# hacker-boards-refactor.net
KiCad netlist of a schematic drawn in EAGLE
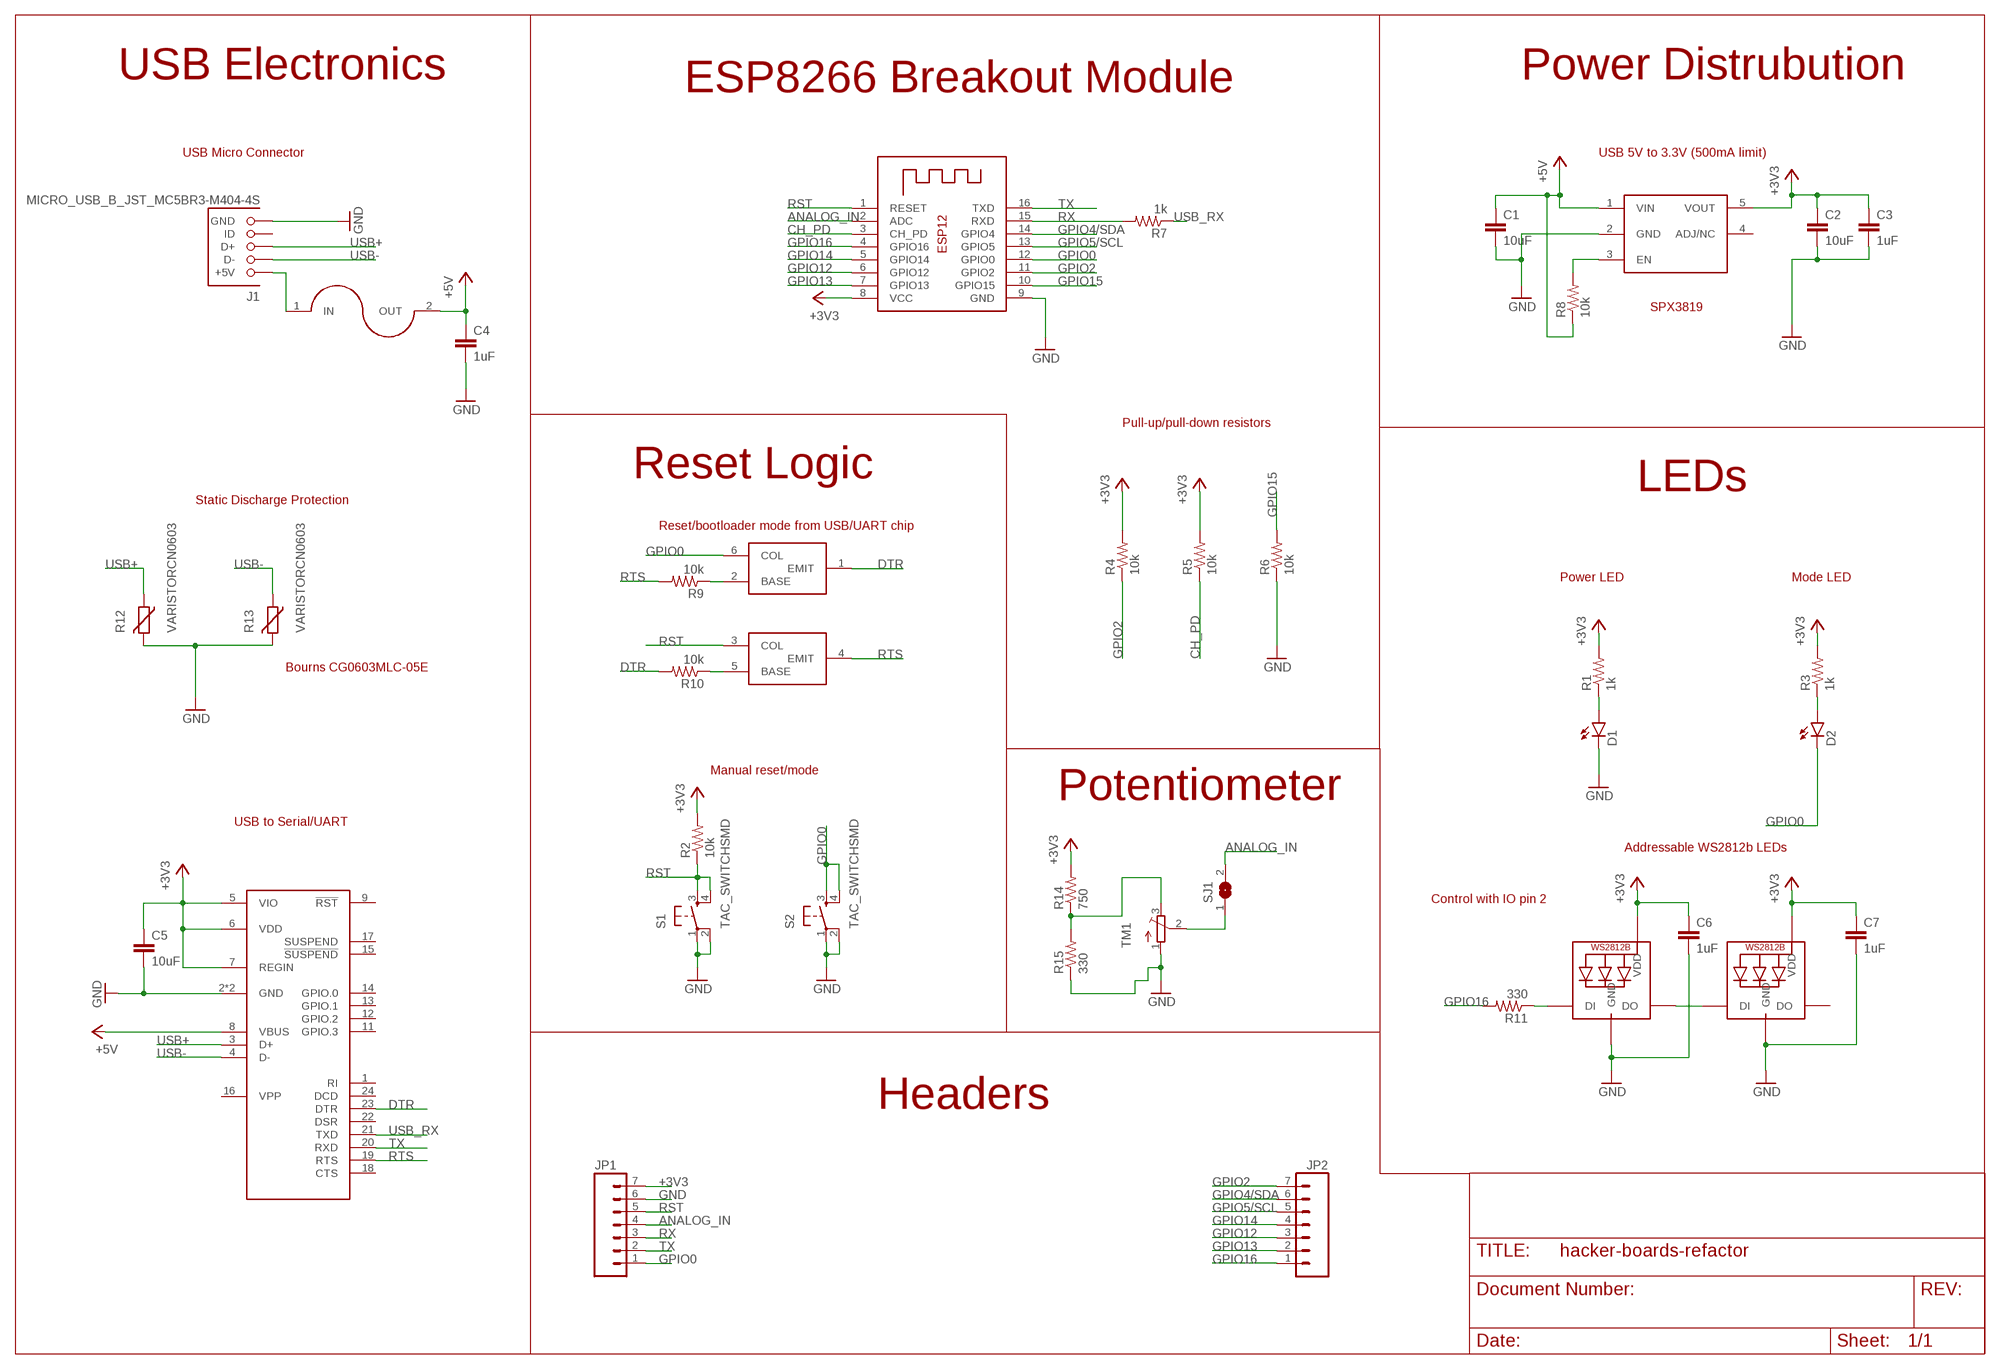
[diagram p0: schematic, sheet 1]

(export (version "E")
  (design (tool "Eeschema 10.0.6"))
  (components
    (comp (ref "C1")
      (value "10uF")
      (footprint "eagle-import:C0805")
      (libsource (lib "eagle-import") (part "C0805"))
    )
    (comp (ref "C2")
      (value "10uF")
      (footprint "eagle-import:C0805")
      (libsource (lib "eagle-import") (part "C0805"))
    )
    (comp (ref "C3")
      (value "1uF")
      (footprint "eagle-import:C0805")
      (libsource (lib "eagle-import") (part "C0805"))
    )
    (comp (ref "C4")
      (value "1uF")
      (footprint "eagle-import:C0805")
      (libsource (lib "eagle-import") (part "C0805"))
    )
    (comp (ref "C5")
      (value "10uF")
      (footprint "eagle-import:C0805")
      (libsource (lib "eagle-import") (part "C0805"))
    )
    (comp (ref "C6")
      (value "1uF")
      (footprint "eagle-import:C0805")
      (libsource (lib "eagle-import") (part "C0805"))
    )
    (comp (ref "C7")
      (value "1uF")
      (footprint "eagle-import:C0805")
      (libsource (lib "eagle-import") (part "C0805"))
    )
    (comp (ref "D1")
      (value "LED0603")
      (footprint "eagle-import:LED-0603")
      (libsource (lib "eagle-import") (part "LED0603"))
    )
    (comp (ref "D2")
      (value "LED0603")
      (footprint "eagle-import:LED-0603")
      (libsource (lib "eagle-import") (part "LED0603"))
    )
    (comp (ref "J1")
      (value "MICRO_USB_B_JST_MC5BR3-M404-4S")
      (footprint "eagle-import:USB_MICRO_B-JST-MC5BR3-M404-4S-TB")
      (libsource (lib "eagle-import") (part "MICRO_USB_B_JST_MC5BR3-M404-4S"))
    )
    (comp (ref "JP1")
      (value "M07LONGPADS")
      (footprint "eagle-import:1X07_LONGPADS")
      (libsource (lib "eagle-import") (part "M07LONGPADS"))
    )
    (comp (ref "JP2")
      (value "M07LONGPADS")
      (footprint "eagle-import:1X07_LONGPADS")
      (libsource (lib "eagle-import") (part "M07LONGPADS"))
    )
    (comp (ref "LED1")
      (value "WS2812B5050")
      (footprint "eagle-import:WS2812B")
      (libsource (lib "eagle-import") (part "WS2812B5050"))
    )
    (comp (ref "LED2")
      (value "WS2812B5050")
      (footprint "eagle-import:WS2812B")
      (libsource (lib "eagle-import") (part "WS2812B5050"))
    )
    (comp (ref "R1")
      (value "1k")
      (footprint "eagle-import:R0805")
      (libsource (lib "eagle-import") (part "R-US_R0805"))
    )
    (comp (ref "R2")
      (value "10k")
      (footprint "eagle-import:R0805")
      (libsource (lib "eagle-import") (part "R-US_R0805"))
    )
    (comp (ref "R3")
      (value "1k")
      (footprint "eagle-import:R0805")
      (libsource (lib "eagle-import") (part "R-US_R0805"))
    )
    (comp (ref "R4")
      (value "10k")
      (footprint "eagle-import:R0805")
      (libsource (lib "eagle-import") (part "R-US_R0805"))
    )
    (comp (ref "R5")
      (value "10k")
      (footprint "eagle-import:R0805")
      (libsource (lib "eagle-import") (part "R-US_R0805"))
    )
    (comp (ref "R6")
      (value "10k")
      (footprint "eagle-import:R0805")
      (libsource (lib "eagle-import") (part "R-US_R0805"))
    )
    (comp (ref "R7")
      (value "1k")
      (footprint "eagle-import:R0805")
      (libsource (lib "eagle-import") (part "R-US_R0805"))
    )
    (comp (ref "R8")
      (value "10k")
      (footprint "eagle-import:R0805")
      (libsource (lib "eagle-import") (part "R-US_R0805"))
    )
    (comp (ref "R9")
      (value "10k")
      (footprint "eagle-import:R0805")
      (libsource (lib "eagle-import") (part "R-US_R0805"))
    )
    (comp (ref "R10")
      (value "10k")
      (footprint "eagle-import:R0805")
      (libsource (lib "eagle-import") (part "R-US_R0805"))
    )
    (comp (ref "R11")
      (value "330")
      (footprint "eagle-import:R0805")
      (libsource (lib "eagle-import") (part "R-US_R0805"))
    )
    (comp (ref "R12")
      (value "VARISTORCN0603")
      (footprint "eagle-import:CT_CN0603")
      (libsource (lib "eagle-import") (part "VARISTORCN0603"))
    )
    (comp (ref "R13")
      (value "VARISTORCN0603")
      (footprint "eagle-import:CT_CN0603")
      (libsource (lib "eagle-import") (part "VARISTORCN0603"))
    )
    (comp (ref "R14")
      (value "750")
      (footprint "eagle-import:R0805")
      (libsource (lib "eagle-import") (part "R-US_R0805"))
    )
    (comp (ref "R15")
      (value "330")
      (footprint "eagle-import:R0805")
      (libsource (lib "eagle-import") (part "R-US_R0805"))
    )
    (comp (ref "S1")
      (value "TAC_SWITCHSMD")
      (footprint "eagle-import:TACTILE-SWITCH-SMD")
      (libsource (lib "eagle-import") (part "TAC_SWITCHSMD"))
    )
    (comp (ref "S2")
      (value "TAC_SWITCHSMD")
      (footprint "eagle-import:TACTILE-SWITCH-SMD")
      (libsource (lib "eagle-import") (part "TAC_SWITCHSMD"))
    )
    (comp (ref "SJ1") (value "SJ") (footprint "eagle-import:SJ") (libsource (lib "eagle-import") (part "SJ")))
    (comp (ref "TM1")
      (value "TRIMPOTTC33X")
      (footprint "eagle-import:TC33X")
      (libsource (lib "eagle-import") (part "TRIMPOTTC33X"))
    )
    (comp (ref "U$1")
      (value "USB-FUSE")
      (footprint "eagle-import:L1812")
      (libsource (lib "eagle-import") (part "USB-FUSE"))
    )
    (comp (ref "U$2")
      (value "AP2112")
      (footprint "eagle-import:SOT23-5L")
      (libsource (lib "eagle-import") (part "AP2112"))
    )
    (comp (ref "U$3")
      (value "CP2104")
      (footprint "eagle-import:QFN24_4X4")
      (libsource (lib "eagle-import") (part "CP2104"))
    )
    (comp (ref "U$4")
      (value "MBT3904DW1T1G")
      (footprint "eagle-import:SOT363")
      (libsource (lib "eagle-import") (part "MBT3904DW1T1G"))
    )
    (comp (ref "X1")
      (value "ESP-12")
      (footprint "eagle-import:ESP-12")
      (libsource (lib "eagle-import") (part "ESP-12"))
    )
  )
  (nets
    (net (code "1") (name "+3V3") (class "Default")
      (node (ref "C2") (pin "1") (pinfunction "1_1") (pintype "passive"))
      (node (ref "C3") (pin "1") (pinfunction "1_1") (pintype "passive"))
      (node (ref "C5") (pin "1") (pinfunction "1_1") (pintype "passive"))
      (node (ref "C6") (pin "1") (pinfunction "1_1") (pintype "passive"))
      (node (ref "C7") (pin "1") (pinfunction "1_1") (pintype "passive"))
      (node (ref "JP1") (pin "7") (pinfunction "7_7") (pintype "passive"))
      (node (ref "LED1") (pin "1-VDD") (pinfunction "VDD_1-VDD") (pintype "power_in"))
      (node (ref "LED2") (pin "1-VDD") (pinfunction "VDD_1-VDD") (pintype "power_in"))
      (node (ref "R1") (pin "2") (pinfunction "2_2") (pintype "passive"))
      (node (ref "R14") (pin "2") (pinfunction "2_2") (pintype "passive"))
      (node (ref "R2") (pin "2") (pinfunction "2_2") (pintype "passive"))
      (node (ref "R3") (pin "2") (pinfunction "2_2") (pintype "passive"))
      (node (ref "R4") (pin "2") (pinfunction "2_2") (pintype "passive"))
      (node (ref "R5") (pin "2") (pinfunction "2_2") (pintype "passive"))
      (node (ref "U$2") (pin "5") (pinfunction "VOUT_5") (pintype "bidirectional"))
      (node (ref "U$3") (pin "5") (pinfunction "VIO_5") (pintype "bidirectional"))
      (node (ref "U$3") (pin "6") (pinfunction "VDD_6") (pintype "bidirectional"))
      (node (ref "U$3") (pin "7") (pinfunction "REGIN_7") (pintype "bidirectional"))
      (node (ref "X1") (pin "8") (pinfunction "VCC_8") (pintype "power_in"))
    )
    (net (code "2") (name "+5V") (class "Default")
      (node (ref "C1") (pin "1") (pinfunction "1_1") (pintype "passive"))
      (node (ref "C4") (pin "1") (pinfunction "1_1") (pintype "passive"))
      (node (ref "R8") (pin "1") (pinfunction "1_1") (pintype "passive"))
      (node (ref "U$1") (pin "2") (pinfunction "OUT_2") (pintype "bidirectional"))
      (node (ref "U$2") (pin "1") (pinfunction "VIN_1") (pintype "bidirectional"))
      (node (ref "U$3") (pin "8") (pinfunction "VBUS_8") (pintype "bidirectional"))
    )
    (net (code "3") (name "/ANALOG_IN") (class "Default")
      (node (ref "JP1") (pin "4") (pinfunction "4_4") (pintype "passive"))
      (node (ref "SJ1") (pin "2") (pinfunction "2_2") (pintype "passive"))
      (node (ref "X1") (pin "2") (pinfunction "ADC_2") (pintype "passive"))
    )
    (net (code "4") (name "/CH_PD") (class "Default")
      (node (ref "R5") (pin "1") (pinfunction "1_1") (pintype "passive"))
      (node (ref "X1") (pin "3") (pinfunction "CH_PD_3") (pintype "input"))
    )
    (net (code "5") (name "/DTR") (class "Default")
      (node (ref "R10") (pin "2") (pinfunction "2_2") (pintype "passive"))
      (node (ref "U$3") (pin "23") (pinfunction "DTR_23") (pintype "bidirectional"))
      (node (ref "U$4") (pin "1") (pinfunction "EMIT_1") (pintype "bidirectional"))
    )
    (net (code "6") (name "/GPIO0") (class "Default")
      (node (ref "D2") (pin "C") (pinfunction "C_C") (pintype "passive"))
      (node (ref "JP1") (pin "1") (pinfunction "1_1") (pintype "passive"))
      (node (ref "S2") (pin "3") (pinfunction "3_3") (pintype "passive"))
      (node (ref "S2") (pin "4") (pinfunction "4_4") (pintype "passive"))
      (node (ref "U$4") (pin "6") (pinfunction "COL_6") (pintype "bidirectional"))
      (node (ref "X1") (pin "12") (pinfunction "GPIO0_12") (pintype "bidirectional"))
    )
    (net (code "7") (name "/GPIO2") (class "Default")
      (node (ref "JP2") (pin "7") (pinfunction "7_7") (pintype "passive"))
      (node (ref "R4") (pin "1") (pinfunction "1_1") (pintype "passive"))
      (node (ref "X1") (pin "11") (pinfunction "GPIO2_11") (pintype "bidirectional"))
    )
    (net (code "8") (name "/GPIO4{slash}SDA") (class "Default")
      (node (ref "JP2") (pin "6") (pinfunction "6_6") (pintype "passive"))
      (node (ref "X1") (pin "14") (pinfunction "GPIO4_14") (pintype "bidirectional"))
    )
    (net (code "9") (name "/GPIO5{slash}SCL") (class "Default")
      (node (ref "JP2") (pin "5") (pinfunction "5_5") (pintype "passive"))
      (node (ref "X1") (pin "13") (pinfunction "GPIO5_13") (pintype "bidirectional"))
    )
    (net (code "10") (name "/GPIO12") (class "Default")
      (node (ref "JP2") (pin "3") (pinfunction "3_3") (pintype "passive"))
      (node (ref "X1") (pin "6") (pinfunction "GPIO12_6") (pintype "bidirectional"))
    )
    (net (code "11") (name "/GPIO13") (class "Default")
      (node (ref "JP2") (pin "2") (pinfunction "2_2") (pintype "passive"))
      (node (ref "X1") (pin "7") (pinfunction "GPIO13_7") (pintype "bidirectional"))
    )
    (net (code "12") (name "/GPIO14") (class "Default")
      (node (ref "JP2") (pin "4") (pinfunction "4_4") (pintype "passive"))
      (node (ref "X1") (pin "5") (pinfunction "GPIO14_5") (pintype "bidirectional"))
    )
    (net (code "13") (name "/GPIO15") (class "Default")
      (node (ref "R6") (pin "2") (pinfunction "2_2") (pintype "passive"))
      (node (ref "X1") (pin "10") (pinfunction "GPIO15_10") (pintype "bidirectional"))
    )
    (net (code "14") (name "/GPIO16") (class "Default")
      (node (ref "JP2") (pin "1") (pinfunction "1_1") (pintype "passive"))
      (node (ref "R11") (pin "2") (pinfunction "2_2") (pintype "passive"))
      (node (ref "X1") (pin "4") (pinfunction "GPIO16_4") (pintype "bidirectional"))
    )
    (net (code "15") (name "/RST") (class "Default")
      (node (ref "JP1") (pin "5") (pinfunction "5_5") (pintype "passive"))
      (node (ref "R2") (pin "1") (pinfunction "1_1") (pintype "passive"))
      (node (ref "S1") (pin "3") (pinfunction "3_3") (pintype "passive"))
      (node (ref "S1") (pin "4") (pinfunction "4_4") (pintype "passive"))
      (node (ref "U$4") (pin "3") (pinfunction "COL_3") (pintype "bidirectional"))
      (node (ref "X1") (pin "1") (pinfunction "RESET_1") (pintype "input"))
    )
    (net (code "16") (name "/RTS") (class "Default")
      (node (ref "R9") (pin "2") (pinfunction "2_2") (pintype "passive"))
      (node (ref "U$3") (pin "19") (pinfunction "RTS_19") (pintype "bidirectional"))
      (node (ref "U$4") (pin "4") (pinfunction "EMIT_4") (pintype "bidirectional"))
    )
    (net (code "17") (name "/RX") (class "Default")
      (node (ref "JP1") (pin "3") (pinfunction "3_3") (pintype "passive"))
      (node (ref "R7") (pin "2") (pinfunction "2_2") (pintype "passive"))
      (node (ref "X1") (pin "15") (pinfunction "RXD_15") (pintype "input"))
    )
    (net (code "18") (name "/TX") (class "Default")
      (node (ref "JP1") (pin "2") (pinfunction "2_2") (pintype "passive"))
      (node (ref "U$3") (pin "20") (pinfunction "RXD_20") (pintype "bidirectional"))
      (node (ref "X1") (pin "16") (pinfunction "TXD_16") (pintype "output"))
    )
    (net (code "19") (name "/USB+") (class "Default")
      (node (ref "J1") (pin "3") (pinfunction "D+_3") (pintype "bidirectional"))
      (node (ref "R12") (pin "1") (pinfunction "1_1") (pintype "passive"))
      (node (ref "U$3") (pin "3") (pinfunction "D+_3") (pintype "bidirectional"))
    )
    (net (code "20") (name "/USB-") (class "Default")
      (node (ref "J1") (pin "2") (pinfunction "D-_2") (pintype "bidirectional"))
      (node (ref "R13") (pin "1") (pinfunction "1_1") (pintype "passive"))
      (node (ref "U$3") (pin "4") (pinfunction "D-_4") (pintype "bidirectional"))
    )
    (net (code "21") (name "/USB_RX") (class "Default")
      (node (ref "R7") (pin "1") (pinfunction "1_1") (pintype "passive"))
      (node (ref "U$3") (pin "21") (pinfunction "TXD_21") (pintype "bidirectional"))
    )
    (net (code "22") (name "GND") (class "Default")
      (node (ref "C1") (pin "2") (pinfunction "2_2") (pintype "passive"))
      (node (ref "C2") (pin "2") (pinfunction "2_2") (pintype "passive"))
      (node (ref "C3") (pin "2") (pinfunction "2_2") (pintype "passive"))
      (node (ref "C4") (pin "2") (pinfunction "2_2") (pintype "passive"))
      (node (ref "C5") (pin "2") (pinfunction "2_2") (pintype "passive"))
      (node (ref "C6") (pin "2") (pinfunction "2_2") (pintype "passive"))
      (node (ref "C7") (pin "2") (pinfunction "2_2") (pintype "passive"))
      (node (ref "D1") (pin "C") (pinfunction "C_C") (pintype "passive"))
      (node (ref "J1") (pin "5") (pinfunction "GND_5") (pintype "bidirectional"))
      (node (ref "JP1") (pin "6") (pinfunction "6_6") (pintype "passive"))
      (node (ref "LED1") (pin "3-GND") (pinfunction "GND_3-GND") (pintype "power_in"))
      (node (ref "LED2") (pin "3-GND") (pinfunction "GND_3-GND") (pintype "power_in"))
      (node (ref "R12") (pin "2") (pinfunction "2_2") (pintype "passive"))
      (node (ref "R13") (pin "2") (pinfunction "2_2") (pintype "passive"))
      (node (ref "R15") (pin "1") (pinfunction "1_1") (pintype "passive"))
      (node (ref "R6") (pin "1") (pinfunction "1_1") (pintype "passive"))
      (node (ref "S1") (pin "1") (pinfunction "1_1") (pintype "passive"))
      (node (ref "S1") (pin "2") (pinfunction "2_2") (pintype "passive"))
      (node (ref "S2") (pin "1") (pinfunction "1_1") (pintype "passive"))
      (node (ref "S2") (pin "2") (pinfunction "2_2") (pintype "passive"))
      (node (ref "TM1") (pin "1") (pinfunction "A_1") (pintype "passive"))
      (node (ref "U$2") (pin "2") (pinfunction "GND_2") (pintype "bidirectional"))
      (node (ref "U$3") (pin "2") (pinfunction "GND_2") (pintype "bidirectional"))
      (node (ref "U$3") (pin "25") (pinfunction "GND_25") (pintype "bidirectional"))
      (node (ref "X1") (pin "9") (pinfunction "GND_9") (pintype "power_in"))
    )
    (net (code "23") (name "Net-(D1-PadA)") (class "Default")
      (node (ref "D1") (pin "A") (pinfunction "A_A") (pintype "passive"))
      (node (ref "R1") (pin "1") (pinfunction "1_1") (pintype "passive"))
    )
    (net (code "24") (name "Net-(D2-PadA)") (class "Default")
      (node (ref "D2") (pin "A") (pinfunction "A_A") (pintype "passive"))
      (node (ref "R3") (pin "1") (pinfunction "1_1") (pintype "passive"))
    )
    (net (code "25") (name "Net-(J1-+5V)") (class "Default")
      (node (ref "J1") (pin "1") (pinfunction "+5V_1") (pintype "bidirectional"))
      (node (ref "U$1") (pin "1") (pinfunction "IN_1") (pintype "bidirectional"))
    )
    (net (code "26") (name "Net-(LED1-DI)") (class "Default")
      (node (ref "LED1") (pin "4-DIN") (pinfunction "DI_4-DIN") (pintype "input"))
      (node (ref "R11") (pin "1") (pinfunction "1_1") (pintype "passive"))
    )
    (net (code "27") (name "Net-(LED1-DO)") (class "Default")
      (node (ref "LED1") (pin "2-DOUT") (pinfunction "DO_2-DOUT") (pintype "output"))
      (node (ref "LED2") (pin "4-DIN") (pinfunction "DI_4-DIN") (pintype "input"))
    )
    (net (code "28") (name "Net-(TM1-E)") (class "Default")
      (node (ref "R14") (pin "1") (pinfunction "1_1") (pintype "passive"))
      (node (ref "R15") (pin "2") (pinfunction "2_2") (pintype "passive"))
      (node (ref "TM1") (pin "3") (pinfunction "E_3") (pintype "passive"))
    )
    (net (code "29") (name "Net-(TM1-S)") (class "Default")
      (node (ref "SJ1") (pin "1") (pinfunction "1_1") (pintype "passive"))
      (node (ref "TM1") (pin "2") (pinfunction "S_2") (pintype "passive"))
    )
    (net (code "30") (name "Net-(U$2-EN)") (class "Default")
      (node (ref "R8") (pin "2") (pinfunction "2_2") (pintype "passive"))
      (node (ref "U$2") (pin "3") (pinfunction "EN_3") (pintype "bidirectional"))
    )
    (net (code "31") (name "Net-(U$4A-BASE)") (class "Default")
      (node (ref "R9") (pin "1") (pinfunction "1_1") (pintype "passive"))
      (node (ref "U$4") (pin "2") (pinfunction "BASE_2") (pintype "bidirectional"))
    )
    (net (code "32") (name "Net-(U$4B-BASE)") (class "Default")
      (node (ref "R10") (pin "1") (pinfunction "1_1") (pintype "passive"))
      (node (ref "U$4") (pin "5") (pinfunction "BASE_5") (pintype "bidirectional"))
    )
    (net (code "33") (name "unconnected-(J1-ID-Pad4)") (class "Default")
      (node (ref "J1") (pin "4") (pinfunction "ID_4") (pintype "bidirectional"))
    )
    (net (code "34") (name "unconnected-(LED2-DO-Pad2-DOUT)") (class "Default")
      (node (ref "LED2") (pin "2-DOUT") (pinfunction "DO_2-DOUT") (pintype "output"))
    )
    (net (code "35") (name "unconnected-(U$2-ADJ{slash}NC-Pad4)") (class "Default")
      (node (ref "U$2") (pin "4") (pinfunction "ADJ/NC_4") (pintype "bidirectional"))
    )
    (net (code "36") (name "unconnected-(U$3-CTS-Pad18)") (class "Default")
      (node (ref "U$3") (pin "18") (pinfunction "CTS_18") (pintype "bidirectional"))
    )
    (net (code "37") (name "unconnected-(U$3-DCD-Pad24)") (class "Default")
      (node (ref "U$3") (pin "24") (pinfunction "DCD_24") (pintype "bidirectional"))
    )
    (net (code "38") (name "unconnected-(U$3-DSR-Pad22)") (class "Default")
      (node (ref "U$3") (pin "22") (pinfunction "DSR_22") (pintype "bidirectional"))
    )
    (net (code "39") (name "unconnected-(U$3-GPIO.0-Pad14)") (class "Default")
      (node (ref "U$3") (pin "14") (pinfunction "GPIO.0_14") (pintype "bidirectional"))
    )
    (net (code "40") (name "unconnected-(U$3-GPIO.1-Pad13)") (class "Default")
      (node (ref "U$3") (pin "13") (pinfunction "GPIO.1_13") (pintype "bidirectional"))
    )
    (net (code "41") (name "unconnected-(U$3-GPIO.2-Pad12)") (class "Default")
      (node (ref "U$3") (pin "12") (pinfunction "GPIO.2_12") (pintype "bidirectional"))
    )
    (net (code "42") (name "unconnected-(U$3-GPIO.3-Pad11)") (class "Default")
      (node (ref "U$3") (pin "11") (pinfunction "GPIO.3_11") (pintype "bidirectional"))
    )
    (net (code "43") (name "unconnected-(U$3-RI-Pad1)") (class "Default")
      (node (ref "U$3") (pin "1") (pinfunction "RI_1") (pintype "bidirectional"))
    )
    (net (code "44") (name "unconnected-(U$3-SUSPEND-Pad17)") (class "Default")
      (node (ref "U$3") (pin "17") (pinfunction "SUSPEND_17") (pintype "bidirectional"))
    )
    (net (code "45") (name "unconnected-(U$3-VPP-Pad16)") (class "Default")
      (node (ref "U$3") (pin "16") (pinfunction "VPP_16") (pintype "input"))
    )
    (net (code "46") (name "unconnected-(U$3-~{RST}-Pad9)") (class "Default")
      (node (ref "U$3") (pin "9") (pinfunction "~{RST}_9") (pintype "bidirectional"))
    )
    (net (code "47") (name "unconnected-(U$3-~{SUSPEND}-Pad15)") (class "Default")
      (node (ref "U$3") (pin "15") (pinfunction "~{SUSPEND}_15") (pintype "bidirectional"))
    )
  )
)
